# kamstrup-wifi.net
KiCad netlist of a schematic drawn in EAGLE
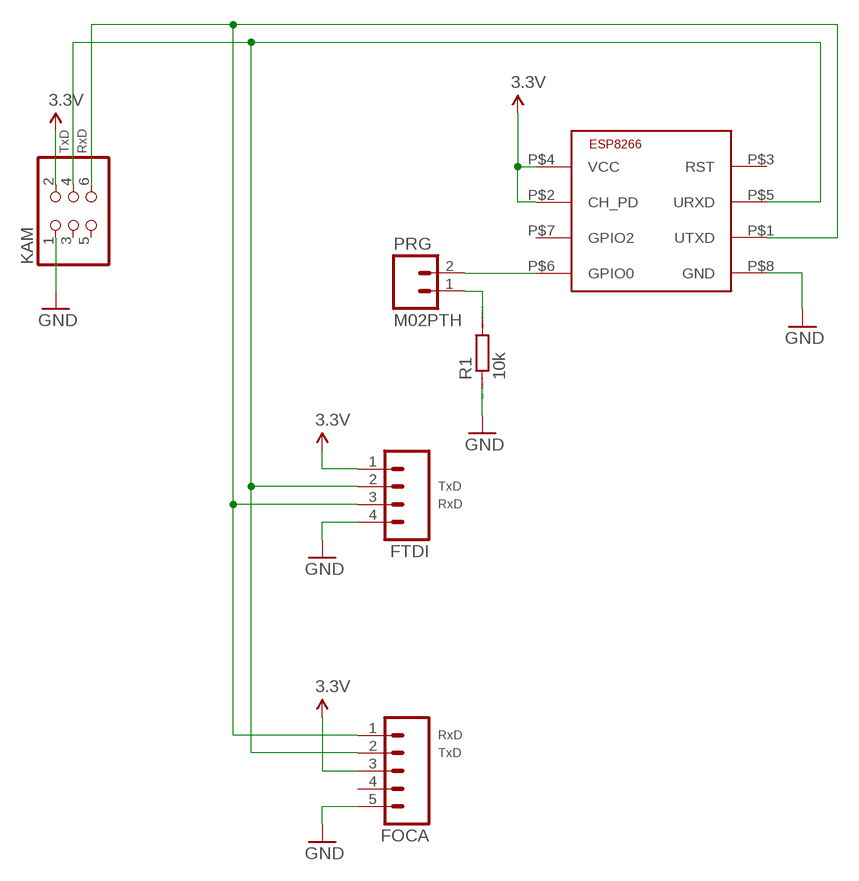
[diagram p0: schematic, sheet 1]

(export (version "E")
  (design (tool "Eeschema 10.0.6"))
  (components
    (comp (ref "FOCA")
      (value "M05PTH")
      (footprint "eagle-import:1X05")
      (libsource (lib "eagle-import") (part "M05PTH"))
    )
    (comp (ref "FTDI")
      (value "M04PTH")
      (footprint "eagle-import:1X04")
      (libsource (lib "eagle-import") (part "M04PTH"))
    )
    (comp (ref "KAM")
      (value "PINHD-2X3")
      (footprint "eagle-import:2X03")
      (libsource (lib "eagle-import") (part "PINHD-2X3"))
    )
    (comp (ref "PRG")
      (value "M02PTH")
      (footprint "eagle-import:1X02")
      (libsource (lib "eagle-import") (part "M02PTH"))
    )
    (comp (ref "R1")
      (value "10k")
      (footprint "eagle-import:M0805")
      (libsource (lib "eagle-import") (part "R-EU_M0805"))
    )
    (comp (ref "U$1")
      (value "ESP8266-01")
      (footprint "eagle-import:ESP-01")
      (libsource (lib "eagle-import") (part "ESP8266-01"))
    )
  )
  (nets
    (net (code "1") (name "3.3V") (class "Default")
      (node (ref "FOCA") (pin "3") (pinfunction "3_3") (pintype "passive"))
      (node (ref "FTDI") (pin "1") (pinfunction "1_1") (pintype "passive"))
      (node (ref "KAM") (pin "2") (pinfunction "2_2") (pintype "passive"))
      (node (ref "U$1") (pin "P$2") (pinfunction "CH_PD_P$2") (pintype "bidirectional"))
      (node (ref "U$1") (pin "P$4") (pinfunction "VCC_P$4") (pintype "bidirectional"))
    )
    (net (code "2") (name "GND") (class "Default")
      (node (ref "FOCA") (pin "5") (pinfunction "5_5") (pintype "passive"))
      (node (ref "FTDI") (pin "4") (pinfunction "4_4") (pintype "passive"))
      (node (ref "KAM") (pin "1") (pinfunction "1_1") (pintype "passive"))
      (node (ref "R1") (pin "1") (pinfunction "1_1") (pintype "passive"))
      (node (ref "U$1") (pin "P$8") (pinfunction "GND_P$8") (pintype "bidirectional"))
    )
    (net (code "3") (name "Net-(PRG-Pad1)") (class "Default")
      (node (ref "PRG") (pin "1") (pinfunction "1_1") (pintype "passive"))
      (node (ref "R1") (pin "2") (pinfunction "2_2") (pintype "passive"))
    )
    (net (code "4") (name "Net-(U$1-GPIO0)") (class "Default")
      (node (ref "PRG") (pin "2") (pinfunction "2_2") (pintype "passive"))
      (node (ref "U$1") (pin "P$6") (pinfunction "GPIO0_P$6") (pintype "bidirectional"))
    )
    (net (code "5") (name "Net-(U$1-URXD)") (class "Default")
      (node (ref "FOCA") (pin "2") (pinfunction "2_2") (pintype "passive"))
      (node (ref "FTDI") (pin "2") (pinfunction "2_2") (pintype "passive"))
      (node (ref "KAM") (pin "4") (pinfunction "4_4") (pintype "passive"))
      (node (ref "U$1") (pin "P$5") (pinfunction "URXD_P$5") (pintype "bidirectional"))
    )
    (net (code "6") (name "Net-(U$1-UTXD)") (class "Default")
      (node (ref "FOCA") (pin "1") (pinfunction "1_1") (pintype "passive"))
      (node (ref "FTDI") (pin "3") (pinfunction "3_3") (pintype "passive"))
      (node (ref "KAM") (pin "6") (pinfunction "6_6") (pintype "passive"))
      (node (ref "U$1") (pin "P$1") (pinfunction "UTXD_P$1") (pintype "bidirectional"))
    )
    (net (code "7") (name "unconnected-(FOCA-Pad4)") (class "Default")
      (node (ref "FOCA") (pin "4") (pinfunction "4_4") (pintype "passive"))
    )
    (net (code "8") (name "unconnected-(KAM-Pad3)") (class "Default")
      (node (ref "KAM") (pin "3") (pinfunction "3_3") (pintype "passive"))
    )
    (net (code "9") (name "unconnected-(KAM-Pad5)") (class "Default")
      (node (ref "KAM") (pin "5") (pinfunction "5_5") (pintype "passive"))
    )
    (net (code "10") (name "unconnected-(U$1-GPIO2-PadP$7)") (class "Default")
      (node (ref "U$1") (pin "P$7") (pinfunction "GPIO2_P$7") (pintype "bidirectional"))
    )
    (net (code "11") (name "unconnected-(U$1-RST-PadP$3)") (class "Default")
      (node (ref "U$1") (pin "P$3") (pinfunction "RST_P$3") (pintype "bidirectional"))
    )
  )
)
